# Injector_1_0v_making.net
KiCad netlist of a schematic drawn in EAGLE
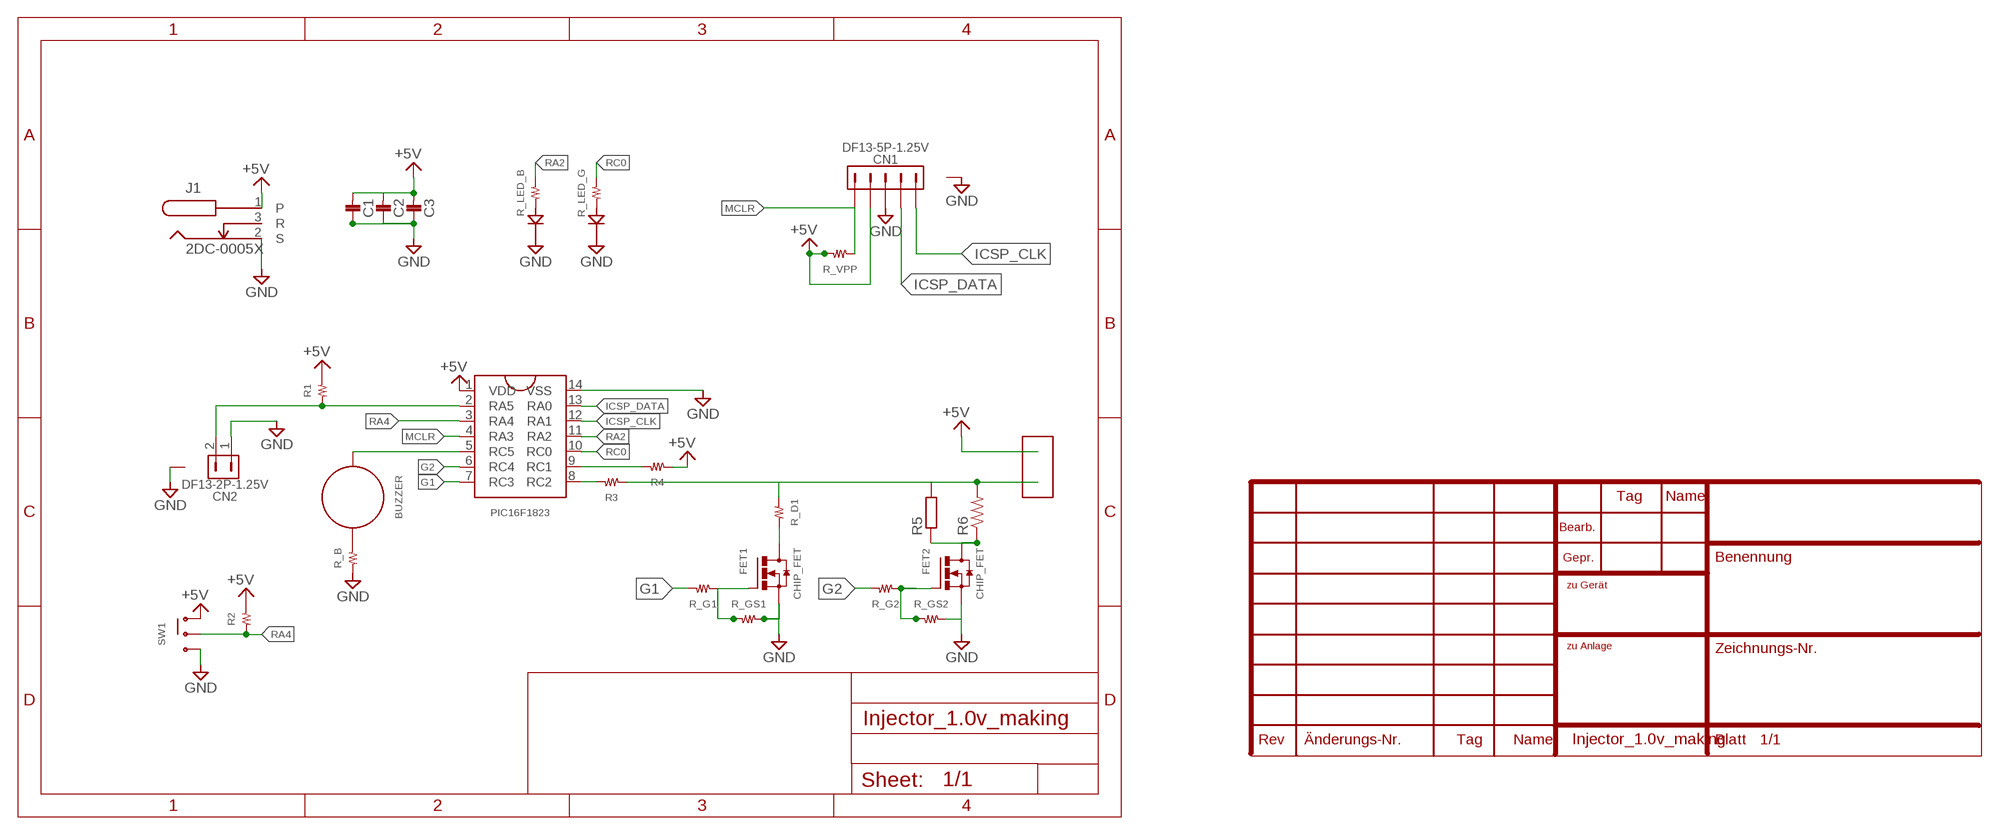
[diagram p0: schematic, sheet 1]

(export (version "E")
  (design (tool "Eeschema 10.0.6"))
  (components
    (comp (ref "BUZZER")
      (value "PKM13EPYH")
      (footprint "eagle-import:PKM13EPYH")
      (libsource (lib "eagle-import") (part "PKM13EPYH"))
    )
    (comp (ref "C1")
      (value "1608")
      (footprint "eagle-import:1608")
      (libsource (lib "eagle-import") (part "1608"))
    )
    (comp (ref "C2")
      (value "1608")
      (footprint "eagle-import:1608")
      (libsource (lib "eagle-import") (part "1608"))
    )
    (comp (ref "C3")
      (value "3225")
      (footprint "eagle-import:3225")
      (libsource (lib "eagle-import") (part "3225"))
    )
    (comp (ref "CN1")
      (value "DF13-5P-1.25V")
      (footprint "eagle-import:DF13C-5P-1.25V")
      (libsource (lib "eagle-import") (part "DF13-5P-1.25V"))
    )
    (comp (ref "CN2")
      (value "DF13-2P-1.25V")
      (footprint "eagle-import:DF13C-2P-1.25V")
      (libsource (lib "eagle-import") (part "DF13-2P-1.25V"))
    )
    (comp (ref "CN3")
      (value "PIN_HEADER_2")
      (footprint "eagle-import:PIN_HEADER_2S")
      (libsource (lib "eagle-import") (part "PIN_HEADER_2"))
    )
    (comp (ref "FET1")
      (value "CHIP_FET")
      (footprint "eagle-import:SOT23")
      (libsource (lib "eagle-import") (part "CHIP_FET"))
    )
    (comp (ref "FET2")
      (value "CHIP_FET")
      (footprint "eagle-import:SOT23")
      (libsource (lib "eagle-import") (part "CHIP_FET"))
    )
    (comp (ref "IC1")
      (value "PIC16F1823")
      (footprint "eagle-import:TSSOP")
      (libsource (lib "eagle-import") (part "PIC16F1823"))
    )
    (comp (ref "J1")
      (value "2DC-0005X")
      (footprint "eagle-import:2DC-0005D")
      (libsource (lib "eagle-import") (part "2DC-0005X"))
    )
    (comp (ref "LED_B")
      (value "CHIPLED")
      (footprint "eagle-import:1608")
      (libsource (lib "eagle-import") (part "CHIPLED"))
    )
    (comp (ref "LED_G")
      (value "CHIPLED")
      (footprint "eagle-import:1608")
      (libsource (lib "eagle-import") (part "CHIPLED"))
    )
    (comp (ref "R1")
      (value "RESISTOR__SMD")
      (footprint "eagle-import:1608")
      (libsource (lib "eagle-import") (part "RESISTOR__SMD"))
    )
    (comp (ref "R2")
      (value "RESISTOR__SMD")
      (footprint "eagle-import:1608")
      (libsource (lib "eagle-import") (part "RESISTOR__SMD"))
    )
    (comp (ref "R3")
      (value "RESISTOR__SMD")
      (footprint "eagle-import:1608")
      (libsource (lib "eagle-import") (part "RESISTOR__SMD"))
    )
    (comp (ref "R4")
      (value "RESISTOR__SMD")
      (footprint "eagle-import:1608")
      (libsource (lib "eagle-import") (part "RESISTOR__SMD"))
    )
    (comp (ref "R5")
      (value "R-EU_0411/12")
      (footprint "eagle-import:0411_12")
      (libsource (lib "eagle-import") (part "R-EU_0411/12"))
    )
    (comp (ref "R6")
      (value "R-US_0613/15")
      (footprint "eagle-import:P0613_15")
      (libsource (lib "eagle-import") (part "R-US_0613/15"))
    )
    (comp (ref "R_B")
      (value "RESISTOR__SMD")
      (footprint "eagle-import:1608")
      (libsource (lib "eagle-import") (part "RESISTOR__SMD"))
    )
    (comp (ref "R_D1")
      (value "RESISTOR__SMD")
      (footprint "eagle-import:1608")
      (libsource (lib "eagle-import") (part "RESISTOR__SMD"))
    )
    (comp (ref "R_G1")
      (value "RESISTOR__SMD")
      (footprint "eagle-import:1608")
      (libsource (lib "eagle-import") (part "RESISTOR__SMD"))
    )
    (comp (ref "R_G2")
      (value "RESISTOR__SMD")
      (footprint "eagle-import:1608")
      (libsource (lib "eagle-import") (part "RESISTOR__SMD"))
    )
    (comp (ref "R_GS1")
      (value "RESISTOR__SMD")
      (footprint "eagle-import:1608")
      (libsource (lib "eagle-import") (part "RESISTOR__SMD"))
    )
    (comp (ref "R_GS2")
      (value "RESISTOR__SMD")
      (footprint "eagle-import:1608")
      (libsource (lib "eagle-import") (part "RESISTOR__SMD"))
    )
    (comp (ref "R_LED_B")
      (value "RESISTOR__SMD")
      (footprint "eagle-import:1608")
      (libsource (lib "eagle-import") (part "RESISTOR__SMD"))
    )
    (comp (ref "R_LED_G")
      (value "RESISTOR__SMD")
      (footprint "eagle-import:1608")
      (libsource (lib "eagle-import") (part "RESISTOR__SMD"))
    )
    (comp (ref "R_VPP")
      (value "RESISTOR__SMD")
      (footprint "eagle-import:1608")
      (libsource (lib "eagle-import") (part "RESISTOR__SMD"))
    )
    (comp (ref "SW1")
      (value "SSSS213202")
      (footprint "eagle-import:SSSS2")
      (libsource (lib "eagle-import") (part "SSSS213202"))
    )
  )
  (nets
    (net (code "1") (name "+5V") (class "Default")
      (node (ref "C1") (pin "P$2") (pinfunction "2_P$2") (pintype "passive"))
      (node (ref "C2") (pin "P$2") (pinfunction "2_P$2") (pintype "passive"))
      (node (ref "C3") (pin "P$2") (pinfunction "2_P$2") (pintype "passive"))
      (node (ref "CN1") (pin "P$2") (pinfunction "2_P$2") (pintype "passive"))
      (node (ref "CN3") (pin "P$2") (pinfunction "P$2_P$2") (pintype "bidirectional"))
      (node (ref "IC1") (pin "1") (pinfunction "VDD_1") (pintype "bidirectional"))
      (node (ref "J1") (pin "1") (pinfunction "P_1") (pintype "power_in"))
      (node (ref "R1") (pin "2") (pinfunction "P$2_2") (pintype "passive"))
      (node (ref "R2") (pin "2") (pinfunction "P$2_2") (pintype "passive"))
      (node (ref "R4") (pin "1") (pinfunction "P$1_1") (pintype "passive"))
      (node (ref "R_VPP") (pin "2") (pinfunction "P$2_2") (pintype "passive"))
      (node (ref "SW1") (pin "1") (pinfunction "P$1_1") (pintype "bidirectional"))
      (node (ref "SW1") (pin "1-") (pinfunction "P$1_1-") (pintype "bidirectional"))
    )
    (net (code "2") (name "G1") (class "Default")
      (node (ref "IC1") (pin "7") (pinfunction "RC3_7") (pintype "bidirectional"))
      (node (ref "R_G1") (pin "2") (pinfunction "P$2_2") (pintype "passive"))
    )
    (net (code "3") (name "G2") (class "Default")
      (node (ref "IC1") (pin "6") (pinfunction "RC4_6") (pintype "bidirectional"))
      (node (ref "R_G2") (pin "2") (pinfunction "P$2_2") (pintype "passive"))
    )
    (net (code "4") (name "GND") (class "Default")
      (node (ref "C1") (pin "P$1") (pinfunction "1_P$1") (pintype "passive"))
      (node (ref "C2") (pin "P$1") (pinfunction "1_P$1") (pintype "passive"))
      (node (ref "C3") (pin "P$1") (pinfunction "1_P$1") (pintype "passive"))
      (node (ref "CN1") (pin "M$0") (pinfunction "G_M$0") (pintype "bidirectional"))
      (node (ref "CN1") (pin "M$1") (pinfunction "G_M$1") (pintype "bidirectional"))
      (node (ref "CN1") (pin "P$3") (pinfunction "3_P$3") (pintype "passive"))
      (node (ref "CN1") (pin "P$6") (pinfunction "G_P$6") (pintype "bidirectional"))
      (node (ref "CN1") (pin "P$7") (pinfunction "G_P$7") (pintype "bidirectional"))
      (node (ref "CN2") (pin "1") (pinfunction "1_1") (pintype "passive"))
      (node (ref "CN2") (pin "G1") (pinfunction "G_G1") (pintype "bidirectional"))
      (node (ref "CN2") (pin "G2") (pinfunction "G_G2") (pintype "bidirectional"))
      (node (ref "CN2") (pin "M$0") (pinfunction "G_M$0") (pintype "bidirectional"))
      (node (ref "CN2") (pin "M$1") (pinfunction "G_M$1") (pintype "bidirectional"))
      (node (ref "FET1") (pin "2") (pinfunction "S_2") (pintype "passive"))
      (node (ref "FET2") (pin "2") (pinfunction "S_2") (pintype "passive"))
      (node (ref "IC1") (pin "14") (pinfunction "VSS_14") (pintype "bidirectional"))
      (node (ref "J1") (pin "2") (pinfunction "S_2") (pintype "power_in"))
      (node (ref "LED_B") (pin "2") (pinfunction "K_2") (pintype "bidirectional"))
      (node (ref "LED_G") (pin "2") (pinfunction "K_2") (pintype "bidirectional"))
      (node (ref "R_B") (pin "1") (pinfunction "P$1_1") (pintype "passive"))
      (node (ref "R_GS1") (pin "2") (pinfunction "P$2_2") (pintype "passive"))
      (node (ref "R_GS2") (pin "2") (pinfunction "P$2_2") (pintype "passive"))
      (node (ref "SW1") (pin "3") (pinfunction "P$3_3") (pintype "bidirectional"))
      (node (ref "SW1") (pin "3-") (pinfunction "P$3_3-") (pintype "bidirectional"))
    )
    (net (code "5") (name "ICSP_CLK") (class "Default")
      (node (ref "CN1") (pin "P$5") (pinfunction "5_P$5") (pintype "passive"))
      (node (ref "IC1") (pin "12") (pinfunction "RA1_12") (pintype "bidirectional"))
    )
    (net (code "6") (name "ICSP_DATA") (class "Default")
      (node (ref "CN1") (pin "P$4") (pinfunction "4_P$4") (pintype "passive"))
      (node (ref "IC1") (pin "13") (pinfunction "RA0_13") (pintype "bidirectional"))
    )
    (net (code "7") (name "MCLR") (class "Default")
      (node (ref "CN1") (pin "P$1") (pinfunction "1_P$1") (pintype "passive"))
      (node (ref "IC1") (pin "4") (pinfunction "RA3_4") (pintype "bidirectional"))
      (node (ref "R_VPP") (pin "1") (pinfunction "P$1_1") (pintype "passive"))
    )
    (net (code "8") (name "Net-(FET1-D)") (class "Default")
      (node (ref "FET1") (pin "3") (pinfunction "D_3") (pintype "passive"))
      (node (ref "R_D1") (pin "2") (pinfunction "P$2_2") (pintype "passive"))
    )
    (net (code "9") (name "Net-(FET1-G)") (class "Default")
      (node (ref "FET1") (pin "1") (pinfunction "G_1") (pintype "passive"))
      (node (ref "R_G1") (pin "1") (pinfunction "P$1_1") (pintype "passive"))
      (node (ref "R_GS1") (pin "1") (pinfunction "P$1_1") (pintype "passive"))
    )
    (net (code "10") (name "Net-(FET2-D)") (class "Default")
      (node (ref "FET2") (pin "3") (pinfunction "D_3") (pintype "passive"))
      (node (ref "R5") (pin "1") (pinfunction "1_1") (pintype "passive"))
      (node (ref "R6") (pin "1") (pinfunction "1_1") (pintype "passive"))
    )
    (net (code "11") (name "Net-(FET2-G)") (class "Default")
      (node (ref "FET2") (pin "1") (pinfunction "G_1") (pintype "passive"))
      (node (ref "R_G2") (pin "1") (pinfunction "P$1_1") (pintype "passive"))
      (node (ref "R_GS2") (pin "1") (pinfunction "P$1_1") (pintype "passive"))
    )
    (net (code "12") (name "Net-(IC1-RA5)") (class "Default")
      (node (ref "CN2") (pin "2") (pinfunction "2_2") (pintype "passive"))
      (node (ref "IC1") (pin "2") (pinfunction "RA5_2") (pintype "bidirectional"))
      (node (ref "R1") (pin "1") (pinfunction "P$1_1") (pintype "passive"))
    )
    (net (code "13") (name "Net-(IC1-RC1)") (class "Default")
      (node (ref "IC1") (pin "9") (pinfunction "RC1_9") (pintype "bidirectional"))
      (node (ref "R4") (pin "2") (pinfunction "P$2_2") (pintype "passive"))
    )
    (net (code "14") (name "Net-(IC1-RC2)") (class "Default")
      (node (ref "IC1") (pin "8") (pinfunction "RC2_8") (pintype "bidirectional"))
      (node (ref "R3") (pin "2") (pinfunction "P$2_2") (pintype "passive"))
    )
    (net (code "15") (name "Net-(IC1-RC5)") (class "Default")
      (node (ref "BUZZER") (pin "P$1") (pinfunction "P$1_P$1") (pintype "bidirectional"))
      (node (ref "IC1") (pin "5") (pinfunction "RC5_5") (pintype "bidirectional"))
    )
    (net (code "16") (name "Net-(LED_B-A)") (class "Default")
      (node (ref "LED_B") (pin "1") (pinfunction "A_1") (pintype "bidirectional"))
      (node (ref "R_LED_B") (pin "1") (pinfunction "P$1_1") (pintype "passive"))
    )
    (net (code "17") (name "Net-(LED_G-A)") (class "Default")
      (node (ref "LED_G") (pin "1") (pinfunction "A_1") (pintype "bidirectional"))
      (node (ref "R_LED_G") (pin "1") (pinfunction "P$1_1") (pintype "passive"))
    )
    (net (code "18") (name "Net-(R3-P$1)") (class "Default")
      (node (ref "CN3") (pin "P$1") (pinfunction "P$1_P$1") (pintype "bidirectional"))
      (node (ref "R3") (pin "1") (pinfunction "P$1_1") (pintype "passive"))
      (node (ref "R5") (pin "2") (pinfunction "2_2") (pintype "passive"))
      (node (ref "R6") (pin "2") (pinfunction "2_2") (pintype "passive"))
      (node (ref "R_D1") (pin "1") (pinfunction "P$1_1") (pintype "passive"))
    )
    (net (code "19") (name "Net-(R_B-P$2)") (class "Default")
      (node (ref "BUZZER") (pin "P$2") (pinfunction "P$2_P$2") (pintype "bidirectional"))
      (node (ref "R_B") (pin "2") (pinfunction "P$2_2") (pintype "passive"))
    )
    (net (code "20") (name "RA2") (class "Default")
      (node (ref "IC1") (pin "11") (pinfunction "RA2_11") (pintype "bidirectional"))
      (node (ref "R_LED_B") (pin "2") (pinfunction "P$2_2") (pintype "passive"))
    )
    (net (code "21") (name "RA4") (class "Default")
      (node (ref "IC1") (pin "3") (pinfunction "RA4_3") (pintype "bidirectional"))
      (node (ref "R2") (pin "1") (pinfunction "P$1_1") (pintype "passive"))
      (node (ref "SW1") (pin "2") (pinfunction "P$2_2") (pintype "bidirectional"))
      (node (ref "SW1") (pin "2-") (pinfunction "P$2_2-") (pintype "bidirectional"))
    )
    (net (code "22") (name "RC0") (class "Default")
      (node (ref "IC1") (pin "10") (pinfunction "RC0_10") (pintype "bidirectional"))
      (node (ref "R_LED_G") (pin "2") (pinfunction "P$2_2") (pintype "passive"))
    )
    (net (code "23") (name "unconnected-(J1-R-Pad3)") (class "Default")
      (node (ref "J1") (pin "3") (pinfunction "R_3") (pintype "input"))
    )
  )
)
